# Un_interruptable_power_supply_180534N_Sc.net
KiCad netlist of a schematic drawn in Altium Designer
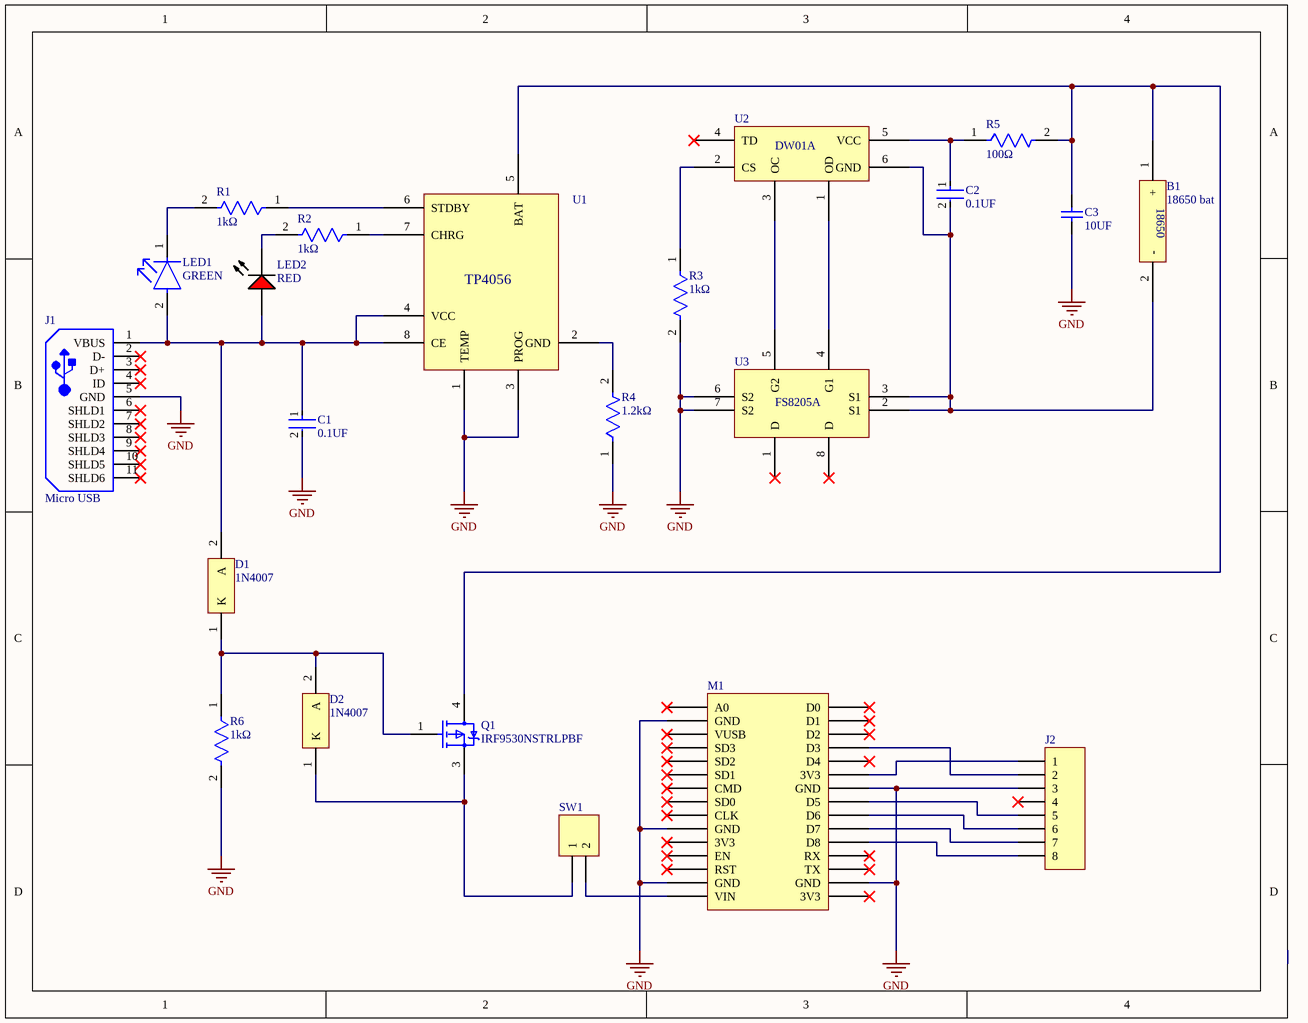
[diagram p0: Un_interruptable_power_supply_180534N_Schematic.SchDoc]

(export (version "E")
  (design (tool "Eeschema 10.0.6"))
  (components
    (comp (ref "B1")
      (value "18650 bat")
      (footprint "18650 Battery connect")
      (libsource (lib "Un_interruptable_power_supply_180534N_Schematic_Library") (part "18650 battery"))
    )
    (comp (ref "C1")
      (value "0.1UF")
      (footprint "FP-C0603C-CF-MFG")
      (description "CAP CER 0.1UF 50V X7R 0603")
      (fields (field (name "TOLERANCE") "0.1") (field (name "MANUFACTURER") "KEMET"))
      (libsource (lib "Altium Content Vault") (part "b4654b650e69147ec39a6b967a45e02"))
    )
    (comp (ref "C2")
      (value "0.1UF")
      (footprint "FP-C0603C-CF-MFG")
      (description "CAP CER 0.1UF 50V X7R 0603")
      (fields (field (name "TOLERANCE") "0.1") (field (name "MANUFACTURER") "KEMET"))
      (libsource (lib "Altium Content Vault") (part "b4654b650e69147ec39a6b967a45e02"))
    )
    (comp (ref "C3")
      (value "10UF")
      (footprint "MURA-0805_H_1.35_M")
      (description "CAP, Ceramic, 10 uF, 10%, 10 V, 0805, RoHS, Tape and Reel")
      (fields (field (name "MANUFACTURER") "Murata") (field (name "TOLERANCE") "±10%"))
      (libsource (lib "Altium Content Vault") (part "CAP-NP-2"))
    )
    (comp (ref "D1")
      (value "1N4007")
      (footprint "ONSC-AXIAL_LEAD-2-59-10_P")
      (description "Standard Recovery Rectifier, 2-Pin Axial_Lead, Pb-Free, Bulk Bag")
      (fields (field (name "MANUFACTURER") "On Semiconductor"))
      (libsource (lib "Altium Content Vault") (part "ONSC-D-K1A2-2_A"))
    )
    (comp (ref "D2")
      (value "1N4007")
      (footprint "ONSC-AXIAL_LEAD-2-59-10_P")
      (description "Standard Recovery Rectifier, 2-Pin Axial_Lead, Pb-Free, Bulk Bag")
      (fields (field (name "MANUFACTURER") "On Semiconductor"))
      (libsource (lib "Altium Content Vault") (part "ONSC-D-K1A2-2_A"))
    )
    (comp (ref "J1")
      (value "Micro USB")
      (footprint "USB-MICRO-B_V")
      (fields (field (name "MANUFACTURER") "Molex"))
      (libsource (lib "Altium Content Vault") (part "USB-5-6SHLD"))
    )
    (comp (ref "J2")
      (value "Header 8")
      (footprint "HDR1X8")
      (description "Header, 8-Pin")
      (fields (field (name "PUBLISHER") "Altium Limited"))
      (libsource (lib "Miscellaneous Connectors") (part "Header 8"))
    )
    (comp (ref "LED1")
      (value "GREEN")
      (footprint "FP-LTST-C190GKT-MFG")
      (description "LED GREEN CLEAR CHIP SMD")
      (fields (field (name "VOLTAGE") "2V"))
      (libsource (lib "Altium Content Vault") (part "8706943c75ba83719d021d2fdc84c58"))
    )
    (comp (ref "LED2")
      (value "RED")
      (footprint "AVAG-HSMX-C190_V")
      (description "LED Uni-Color Red, 65 mW, 20 mA, -40 to 85 degC, 2-Pin SMD, RoHS, Tape and Reel")
      (libsource (lib "Altium Content Vault") (part "LED-RED-AK-2"))
    )
    (comp (ref "M1")
      (value "NodeMCU V1.0 ESP-12E_1")
      (footprint "LoLin NodeMcu V3")
      (description "LoLin NodeMCU V3")
      (libsource (lib "NodeMCU-esp8266") (part "NodeMCU V1.0 ESP-12E_1"))
    )
    (comp (ref "Q1")
      (value "IRF9530NSTRLPBF")
      (footprint "FP-PG-TO263-3-MFG")
      (description "MOSFET P-CH 100V 14A D2PAK")
      (libsource (lib "Altium Content Vault") (part "57f8e05cbe49cb42adda74fd57946b4"))
    )
    (comp (ref "R1")
      (value "1kΩ")
      (footprint "FP-CRCW0603-e3-MFG")
      (description "RES Thick Film, 1kΩ, 1%, 0.1W, 100ppm/°C, 0603")
      (fields (field (name "TOLERANCE") "1%"))
      (libsource (lib "Altium Content Vault") (part "1029c3af85768c4190bb7ad29bc67b5"))
    )
    (comp (ref "R2")
      (value "1kΩ")
      (footprint "FP-CRCW0603-e3-MFG")
      (description "RES Thick Film, 1kΩ, 1%, 0.1W, 100ppm/°C, 0603")
      (fields (field (name "TOLERANCE") "1%"))
      (libsource (lib "Altium Content Vault") (part "1029c3af85768c4190bb7ad29bc67b5"))
    )
    (comp (ref "R3")
      (value "1kΩ")
      (footprint "FP-CRCW0603-e3-MFG")
      (description "RES Thick Film, 1kΩ, 1%, 0.1W, 100ppm/°C, 0603")
      (fields (field (name "TOLERANCE") "1%"))
      (libsource (lib "Altium Content Vault") (part "1029c3af85768c4190bb7ad29bc67b5"))
    )
    (comp (ref "R4")
      (value "1.2kΩ")
      (footprint "FP-CRCW0603-e3-MFG")
      (description "RES Thick Film, 1.2kΩ, 1%, 0.1W, 100ppm/°C, 0603")
      (fields (field (name "TOLERANCE") "1%"))
      (libsource (lib "Altium Content Vault") (part "1029c3af85768c4190bb7ad29bc67b5"))
    )
    (comp (ref "R5")
      (value "100Ω")
      (footprint "FP-CRCW0402-e3-IPC_C")
      (description "RES Thick Film, 100Ω, 1%, 0.063W, 100ppm/°C, 0402")
      (fields (field (name "TOLERANCE") "1%"))
      (libsource (lib "Altium Content Vault") (part "1029c3af85768c4190bb7ad29bc67b5"))
    )
    (comp (ref "R6")
      (value "1kΩ")
      (footprint "FP-CRCW0603-e3-MFG")
      (description "RES Thick Film, 1kΩ, 1%, 0.1W, 100ppm/°C, 0603")
      (fields (field (name "TOLERANCE") "1%"))
      (libsource (lib "Altium Content Vault") (part "1029c3af85768c4190bb7ad29bc67b5"))
    )
    (comp (ref "SW1")
      (value "Header 2")
      (footprint "HDR1X2")
      (description "Header, 2-Pin")
      (fields (field (name "PUBLISHER") "Altium Limited"))
      (libsource (lib "Miscellaneous Connectors") (part "Header 2"))
    )
    (comp (ref "U1")
      (value "TP4056")
      (footprint "TP4056 IC - SOIC_8 Package")
      (libsource (lib "Un_interruptable_power_supply_180534N_Schematic_Library") (part "TP4056"))
    )
    (comp (ref "U2")
      (value "DW01A")
      (footprint "DW01A - SOT 23-6 PACKAGE")
      (description "18650 Battery Protection IC/ Provide over current, over charge and over discharge protection")
      (libsource (lib "Un_interruptable_power_supply_180534N_Schematic_Library") (part "DW01A"))
    )
    (comp (ref "U3")
      (value "FS8205A")
      (footprint "FS8205A - TSSOP-8 PACKAGE")
      (description "Dual N channel MOSFET")
      (libsource (lib "Un_interruptable_power_supply_180534N_Schematic_Library") (part "FS8205A"))
    )
  )
  (nets
    (net (code "1") (name "GND") (class "Default")
      (node (ref "C1") (pin "2") (pinfunction "2_2") (pintype "passive"))
      (node (ref "C3") (pin "1") (pinfunction "1_1") (pintype "passive"))
      (node (ref "J1") (pin "5") (pinfunction "GND_5") (pintype "passive"))
      (node (ref "J2") (pin "3") (pinfunction "3_3") (pintype "passive"))
      (node (ref "M1") (pin "GND") (pinfunction "GND_GND") (pintype "passive"))
      (node (ref "R3") (pin "2") (pinfunction "2_2") (pintype "passive"))
      (node (ref "R4") (pin "1") (pinfunction "1_1") (pintype "passive"))
      (node (ref "R6") (pin "2") (pinfunction "2_2") (pintype "passive"))
      (node (ref "U1") (pin "1") (pinfunction "TEMP_1") (pintype "passive"))
      (node (ref "U1") (pin "3") (pinfunction "PROG_3") (pintype "passive"))
      (node (ref "U3") (pin "6") (pinfunction "S2_6") (pintype "passive"))
      (node (ref "U3") (pin "7") (pinfunction "S2_7") (pintype "passive"))
    )
    (net (code "2") (name "Net-(B1-+)") (class "Default")
      (node (ref "B1") (pin "1") (pinfunction "+_1") (pintype "power_in"))
      (node (ref "C3") (pin "2") (pinfunction "2_2") (pintype "passive"))
      (node (ref "Q1") (pin "4") (pinfunction "D_4") (pintype "passive"))
      (node (ref "R5") (pin "2") (pinfunction "2_2") (pintype "passive"))
      (node (ref "U1") (pin "5") (pinfunction "BAT_5") (pintype "power_in"))
    )
    (net (code "3") (name "Net-(B1--)") (class "Default")
      (node (ref "B1") (pin "2") (pinfunction "-_2") (pintype "power_in"))
      (node (ref "C2") (pin "2") (pinfunction "2_2") (pintype "passive"))
      (node (ref "U2") (pin "6") (pinfunction "GND_6") (pintype "power_in"))
      (node (ref "U3") (pin "2") (pinfunction "S1_2") (pintype "passive"))
      (node (ref "U3") (pin "3") (pinfunction "S1_3") (pintype "passive"))
    )
    (net (code "4") (name "Net-(D1-A)") (class "Default")
      (node (ref "C1") (pin "1") (pinfunction "1_1") (pintype "passive"))
      (node (ref "D1") (pin "2") (pinfunction "A_2") (pintype "passive"))
      (node (ref "J1") (pin "1") (pinfunction "VBUS_1") (pintype "passive"))
      (node (ref "LED1") (pin "2") (pinfunction "A_2") (pintype "passive"))
      (node (ref "LED2") (pin "1") (pinfunction "A_1") (pintype "passive"))
      (node (ref "U1") (pin "4") (pinfunction "VCC_4") (pintype "power_in"))
      (node (ref "U1") (pin "8") (pinfunction "CE_8") (pintype "passive"))
    )
    (net (code "5") (name "Net-(D1-K)") (class "Default")
      (node (ref "D1") (pin "1") (pinfunction "K_1") (pintype "passive"))
      (node (ref "D2") (pin "2") (pinfunction "A_2") (pintype "passive"))
      (node (ref "Q1") (pin "1") (pinfunction "G_1") (pintype "passive"))
      (node (ref "R6") (pin "1") (pinfunction "1_1") (pintype "passive"))
    )
    (net (code "6") (name "Net-(D2-K)") (class "Default")
      (node (ref "D2") (pin "1") (pinfunction "K_1") (pintype "passive"))
      (node (ref "Q1") (pin "3") (pinfunction "S_3") (pintype "passive"))
      (node (ref "SW1") (pin "1") (pinfunction "1_1") (pintype "passive"))
    )
    (net (code "7") (name "Net-(J2-Pad1)") (class "Default")
      (node (ref "J2") (pin "1") (pinfunction "1_1") (pintype "passive"))
      (node (ref "M1") (pin "3V3") (pinfunction "3V3_3V3") (pintype "passive"))
    )
    (net (code "8") (name "Net-(J2-Pad2)") (class "Default")
      (node (ref "J2") (pin "2") (pinfunction "2_2") (pintype "passive"))
      (node (ref "M1") (pin "D3") (pinfunction "D3_D3") (pintype "passive"))
    )
    (net (code "9") (name "Net-(J2-Pad5)") (class "Default")
      (node (ref "J2") (pin "5") (pinfunction "5_5") (pintype "passive"))
      (node (ref "M1") (pin "D5") (pinfunction "D5_D5") (pintype "passive"))
    )
    (net (code "10") (name "Net-(J2-Pad6)") (class "Default")
      (node (ref "J2") (pin "6") (pinfunction "6_6") (pintype "passive"))
      (node (ref "M1") (pin "D6") (pinfunction "D6_D6") (pintype "passive"))
    )
    (net (code "11") (name "Net-(J2-Pad7)") (class "Default")
      (node (ref "J2") (pin "7") (pinfunction "7_7") (pintype "passive"))
      (node (ref "M1") (pin "D7") (pinfunction "D7_D7") (pintype "passive"))
    )
    (net (code "12") (name "Net-(J2-Pad8)") (class "Default")
      (node (ref "J2") (pin "8") (pinfunction "8_8") (pintype "passive"))
      (node (ref "M1") (pin "D8") (pinfunction "D8_D8") (pintype "passive"))
    )
    (net (code "13") (name "Net-(LED1-C)") (class "Default")
      (node (ref "LED1") (pin "1") (pinfunction "C_1") (pintype "passive"))
      (node (ref "R1") (pin "2") (pinfunction "2_2") (pintype "passive"))
    )
    (net (code "14") (name "Net-(LED2-K)") (class "Default")
      (node (ref "LED2") (pin "2") (pinfunction "K_2") (pintype "passive"))
      (node (ref "R2") (pin "2") (pinfunction "2_2") (pintype "passive"))
    )
    (net (code "15") (name "Net-(M1-PadVIN)") (class "Default")
      (node (ref "M1") (pin "VIN") (pinfunction "VIN_VIN") (pintype "passive"))
      (node (ref "SW1") (pin "2") (pinfunction "2_2") (pintype "passive"))
    )
    (net (code "16") (name "Net-(U1-CHRG)") (class "Default")
      (node (ref "R2") (pin "1") (pinfunction "1_1") (pintype "passive"))
      (node (ref "U1") (pin "7") (pinfunction "CHRG_7") (pintype "passive"))
    )
    (net (code "17") (name "Net-(U1-GND)") (class "Default")
      (node (ref "R4") (pin "2") (pinfunction "2_2") (pintype "passive"))
      (node (ref "U1") (pin "2") (pinfunction "GND_2") (pintype "power_in"))
    )
    (net (code "18") (name "Net-(U1-STDBY)") (class "Default")
      (node (ref "R1") (pin "1") (pinfunction "1_1") (pintype "passive"))
      (node (ref "U1") (pin "6") (pinfunction "STDBY_6") (pintype "passive"))
    )
    (net (code "19") (name "Net-(U2-CS)") (class "Default")
      (node (ref "R3") (pin "1") (pinfunction "1_1") (pintype "passive"))
      (node (ref "U2") (pin "2") (pinfunction "CS_2") (pintype "passive"))
    )
    (net (code "20") (name "Net-(U2-OC)") (class "Default")
      (node (ref "U2") (pin "3") (pinfunction "OC_3") (pintype "passive"))
      (node (ref "U3") (pin "5") (pinfunction "G2_5") (pintype "passive"))
    )
    (net (code "21") (name "Net-(U2-OD)") (class "Default")
      (node (ref "U2") (pin "1") (pinfunction "OD_1") (pintype "passive"))
      (node (ref "U3") (pin "4") (pinfunction "G1_4") (pintype "passive"))
    )
    (net (code "22") (name "Net-(U2-VCC)") (class "Default")
      (node (ref "C2") (pin "1") (pinfunction "1_1") (pintype "passive"))
      (node (ref "R5") (pin "1") (pinfunction "1_1") (pintype "passive"))
      (node (ref "U2") (pin "5") (pinfunction "VCC_5") (pintype "power_in"))
    )
    (net (code "23") (name "unconnected-(J1-D+-Pad3)") (class "Default")
      (node (ref "J1") (pin "3") (pinfunction "D+_3") (pintype "passive+no_connect"))
    )
    (net (code "24") (name "unconnected-(J1-D--Pad2)") (class "Default")
      (node (ref "J1") (pin "2") (pinfunction "D-_2") (pintype "passive+no_connect"))
    )
    (net (code "25") (name "unconnected-(J1-ID-Pad4)") (class "Default")
      (node (ref "J1") (pin "4") (pinfunction "ID_4") (pintype "passive+no_connect"))
    )
    (net (code "26") (name "unconnected-(J1-SHLD1-Pad6)") (class "Default")
      (node (ref "J1") (pin "6") (pinfunction "SHLD1_6") (pintype "passive+no_connect"))
    )
    (net (code "27") (name "unconnected-(J1-SHLD2-Pad7)") (class "Default")
      (node (ref "J1") (pin "7") (pinfunction "SHLD2_7") (pintype "passive+no_connect"))
    )
    (net (code "28") (name "unconnected-(J1-SHLD3-Pad8)") (class "Default")
      (node (ref "J1") (pin "8") (pinfunction "SHLD3_8") (pintype "passive+no_connect"))
    )
    (net (code "29") (name "unconnected-(J1-SHLD4-Pad9)") (class "Default")
      (node (ref "J1") (pin "9") (pinfunction "SHLD4_9") (pintype "passive+no_connect"))
    )
    (net (code "30") (name "unconnected-(J1-SHLD5-Pad10)") (class "Default")
      (node (ref "J1") (pin "10") (pinfunction "SHLD5_10") (pintype "passive+no_connect"))
    )
    (net (code "31") (name "unconnected-(J1-SHLD6-Pad11)") (class "Default")
      (node (ref "J1") (pin "11") (pinfunction "SHLD6_11") (pintype "passive+no_connect"))
    )
    (net (code "32") (name "unconnected-(J2-Pad4)") (class "Default")
      (node (ref "J2") (pin "4") (pinfunction "4_4") (pintype "passive+no_connect"))
    )
    (net (code "33") (name "unconnected-(M1-Pad3V3)") (class "Default")
      (node (ref "M1") (pin "3V3") (pinfunction "3V3_3V3") (pintype "passive+no_connect"))
    )
    (net (code "34") (name "unconnected-(M1-Pad3V3)_1") (class "Default")
      (node (ref "M1") (pin "3V3") (pinfunction "3V3_3V3") (pintype "passive+no_connect"))
    )
    (net (code "35") (name "unconnected-(M1-PadA0)") (class "Default")
      (node (ref "M1") (pin "A0") (pinfunction "A0_A0") (pintype "passive+no_connect"))
    )
    (net (code "36") (name "unconnected-(M1-PadCLK)") (class "Default")
      (node (ref "M1") (pin "CLK") (pinfunction "CLK_CLK") (pintype "passive+no_connect"))
    )
    (net (code "37") (name "unconnected-(M1-PadCMD)") (class "Default")
      (node (ref "M1") (pin "CMD") (pinfunction "CMD_CMD") (pintype "passive+no_connect"))
    )
    (net (code "38") (name "unconnected-(M1-PadD0)") (class "Default")
      (node (ref "M1") (pin "D0") (pinfunction "D0_D0") (pintype "passive+no_connect"))
    )
    (net (code "39") (name "unconnected-(M1-PadD1)") (class "Default")
      (node (ref "M1") (pin "D1") (pinfunction "D1_D1") (pintype "passive+no_connect"))
    )
    (net (code "40") (name "unconnected-(M1-PadD2)") (class "Default")
      (node (ref "M1") (pin "D2") (pinfunction "D2_D2") (pintype "passive+no_connect"))
    )
    (net (code "41") (name "unconnected-(M1-PadD4)") (class "Default")
      (node (ref "M1") (pin "D4") (pinfunction "D4_D4") (pintype "passive+no_connect"))
    )
    (net (code "42") (name "unconnected-(M1-PadEN)") (class "Default")
      (node (ref "M1") (pin "EN") (pinfunction "EN_EN") (pintype "passive+no_connect"))
    )
    (net (code "43") (name "unconnected-(M1-PadRST)") (class "Default")
      (node (ref "M1") (pin "RST") (pinfunction "RST_RST") (pintype "passive+no_connect"))
    )
    (net (code "44") (name "unconnected-(M1-PadRX)") (class "Default")
      (node (ref "M1") (pin "RX") (pinfunction "RX_RX") (pintype "passive+no_connect"))
    )
    (net (code "45") (name "unconnected-(M1-PadSD0)") (class "Default")
      (node (ref "M1") (pin "SD0") (pinfunction "SD0_SD0") (pintype "passive+no_connect"))
    )
    (net (code "46") (name "unconnected-(M1-PadSD1)") (class "Default")
      (node (ref "M1") (pin "SD1") (pinfunction "SD1_SD1") (pintype "passive+no_connect"))
    )
    (net (code "47") (name "unconnected-(M1-PadSD2)") (class "Default")
      (node (ref "M1") (pin "SD2") (pinfunction "SD2_SD2") (pintype "passive+no_connect"))
    )
    (net (code "48") (name "unconnected-(M1-PadSD3)") (class "Default")
      (node (ref "M1") (pin "SD3") (pinfunction "SD3_SD3") (pintype "passive+no_connect"))
    )
    (net (code "49") (name "unconnected-(M1-PadTX)") (class "Default")
      (node (ref "M1") (pin "TX") (pinfunction "TX_TX") (pintype "passive+no_connect"))
    )
    (net (code "50") (name "unconnected-(M1-PadVUSB)") (class "Default")
      (node (ref "M1") (pin "VUSB") (pinfunction "VUSB_VUSB") (pintype "passive+no_connect"))
    )
    (net (code "51") (name "unconnected-(U2-TD-Pad4)") (class "Default")
      (node (ref "U2") (pin "4") (pinfunction "TD_4") (pintype "passive+no_connect"))
    )
    (net (code "52") (name "unconnected-(U3-D-Pad1)") (class "Default")
      (node (ref "U3") (pin "1") (pinfunction "D_1") (pintype "passive+no_connect"))
    )
    (net (code "53") (name "unconnected-(U3-D-Pad8)") (class "Default")
      (node (ref "U3") (pin "8") (pinfunction "D_8") (pintype "passive+no_connect"))
    )
  )
)
